# Main.net
KiCad netlist of a schematic drawn in Altium Designer
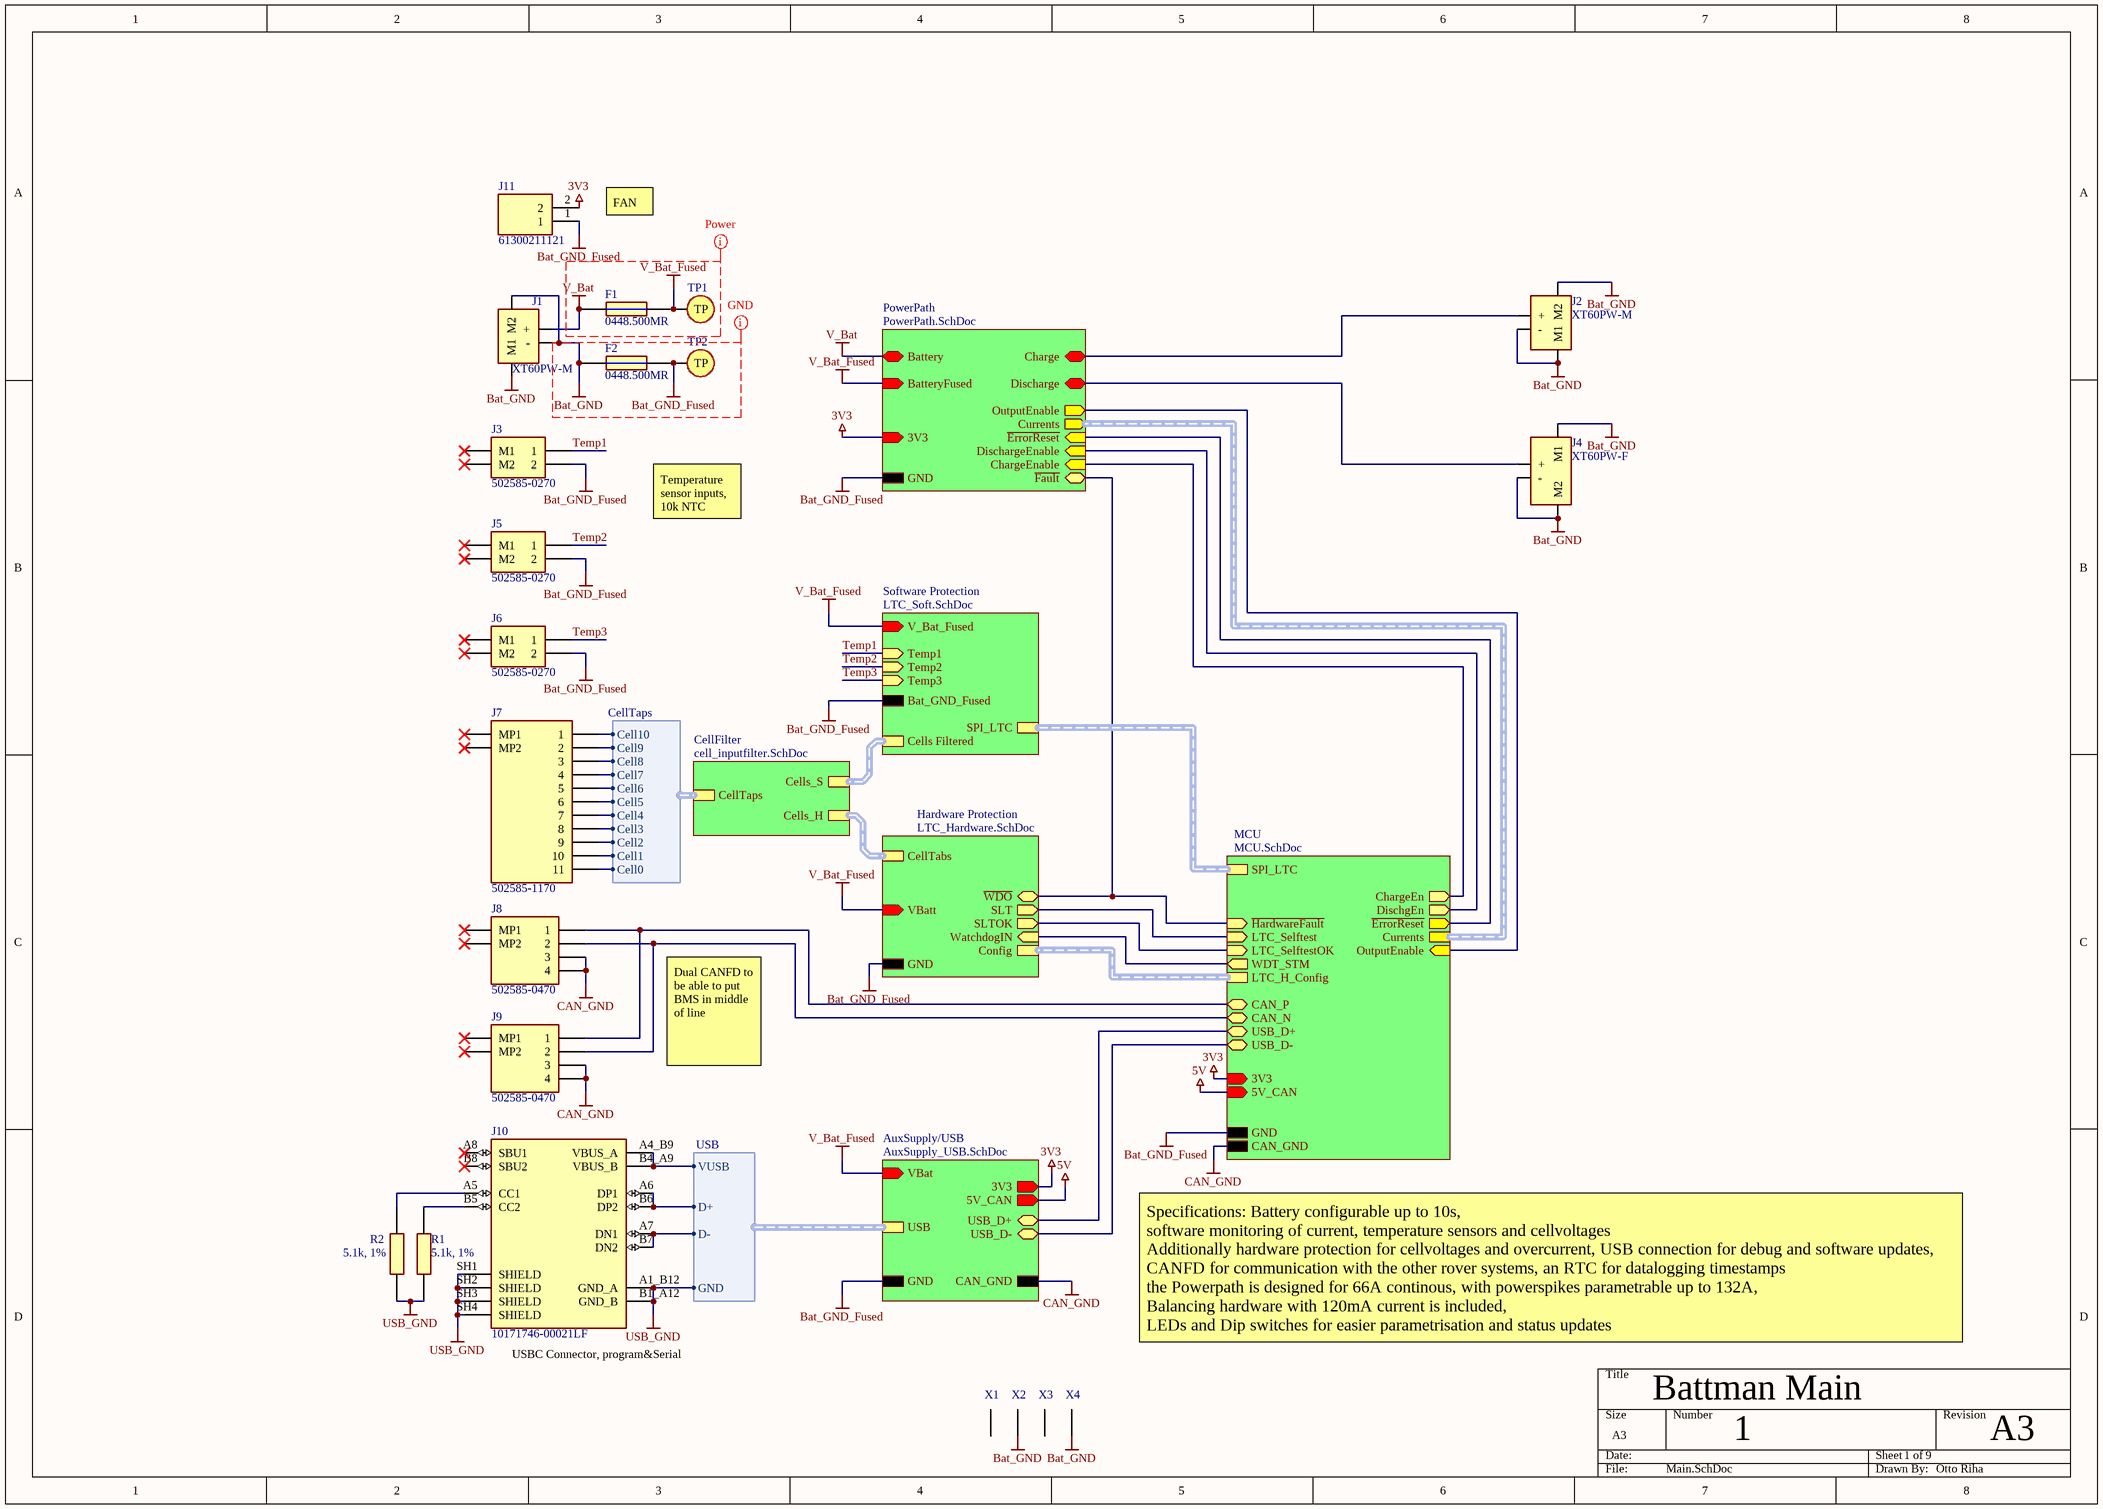
[diagram p0: Main.SchDoc]

(export (version "E")
  (design (tool "Eeschema 10.0.6"))
  (components
    (comp (ref "F1")
      (value "0448.500MR")
      (footprint "SamacSys:FUSC6127X294N")
      (description "Fuse")
      (fields (field (name "MOUSER PART NUMBER") "576-0448.500MR"))
      (libsource (lib "SamacSys") (part "0448.500MR"))
    )
    (comp (ref "F2")
      (value "0448.500MR")
      (footprint "SamacSys:FUSC6127X294N")
      (description "Fuse")
      (fields (field (name "MOUSER PART NUMBER") "576-0448.500MR"))
      (libsource (lib "SamacSys") (part "0448.500MR"))
    )
    (comp (ref "J1")
      (value "XT60PW-M")
      (footprint "SamacSys:XT60PWM")
      (description "Connector")
      (libsource (lib "SamacSys") (part "XT60PW-M"))
    )
    (comp (ref "J2")
      (value "XT60PW-M")
      (footprint "SamacSys:XT60PWM")
      (description "Connector")
      (libsource (lib "") (part "XT60PW-M_1"))
    )
    (comp (ref "J3")
      (value "502585-0270")
      (footprint "SamacSys:5025850270")
      (description "Connector")
      (fields (field (name "MOUSER PART NUMBER") "538-502585-0270"))
      (libsource (lib "SamacSys") (part "502585-0270"))
    )
    (comp (ref "J4")
      (value "XT60PW-F")
      (footprint "SamacSys:XT60PWF")
      (description "Connector")
      (libsource (lib "SamacSys") (part "XT60PW-F"))
    )
    (comp (ref "J5")
      (value "502585-0270")
      (footprint "SamacSys:5025850270")
      (description "Connector")
      (fields (field (name "MOUSER PART NUMBER") "538-502585-0270"))
      (libsource (lib "SamacSys") (part "502585-0270"))
    )
    (comp (ref "J6")
      (value "502585-0270")
      (footprint "SamacSys:5025850270")
      (description "Connector")
      (fields (field (name "MOUSER PART NUMBER") "538-502585-0270"))
      (libsource (lib "SamacSys") (part "502585-0270"))
    )
    (comp (ref "J7")
      (value "502585-1170")
      (footprint "SamacSys:5025851170")
      (description "Connector")
      (fields
        (field (name "MOUSER PART NUMBER") "538-502585-1170")
        (field (name "ARROW PART NUMBER") "502585-1070")
      )
      (libsource (lib "SamacSys") (part "502585-1170"))
    )
    (comp (ref "J8")
      (value "502585-0470")
      (footprint "SamacSys:5025850470")
      (description "Connector")
      (fields (field (name "MOUSER PART NUMBER") "538-502585-0470"))
      (libsource (lib "SamacSys") (part "502585-0470"))
    )
    (comp (ref "J9")
      (value "502585-0470")
      (footprint "SamacSys:5025850470")
      (description "Connector")
      (fields (field (name "MOUSER PART NUMBER") "538-502585-0470"))
      (libsource (lib "SamacSys") (part "502585-0470"))
    )
    (comp (ref "J10")
      (value "10171746-00021LF")
      (footprint "AMPHENOL_10171746-00021LF")
      (fields (field (name "MF") "Amphenol"))
      (libsource (lib "10171746-00021LF") (part "10171746-00021LF"))
    )
    (comp (ref "J11")
      (value "61300211121")
      (footprint "SamacSys:HDRV2W110P0X254_1X2_508X254X854P")
      (description "Connector")
      (fields (field (name "MOUSER PART NUMBER") "710-61300211121"))
      (libsource (lib "*") (part "61300211121"))
    )
    (comp (ref "R1")
      (value "5.1k, 1%")
      (footprint "SamacSys:RESC1608X55N")
      (description "Resistor 5.1k, 1%")
      (fields
        (field (name "MANUFACTURER_PART_NUMBER") "CRCW06035K10FKEBC")
        (field (name "MOUSER PART NUMBER") "71-CRCW06035K10FKEBC")
      )
      (libsource (lib "SamacSys") (part "CRCW06035K10FKEBC"))
    )
    (comp (ref "R2")
      (value "5.1k, 1%")
      (footprint "SamacSys:RESC1608X55N")
      (description "Resistor 5.1k, 1%")
      (fields
        (field (name "MANUFACTURER_PART_NUMBER") "CRCW06035K10FKEBC")
        (field (name "MOUSER PART NUMBER") "71-CRCW06035K10FKEBC")
      )
      (libsource (lib "SamacSys") (part "CRCW06035K10FKEBC"))
    )
    (comp (ref "TP1")
      (value "Testpoint")
      (footprint "Testpoint")
      (libsource (lib "SamacSys") (part "Testpoint"))
    )
    (comp (ref "TP2")
      (value "Testpoint")
      (footprint "Testpoint")
      (libsource (lib "SamacSys") (part "Testpoint"))
    )
    (comp (ref "X1")
      (value "Trou pour Vis M3 celon DIN912")
      (footprint "VisM3")
      (libsource (lib "SamacSys") (part "VisM3"))
    )
    (comp (ref "X2")
      (value "Trou pour Vis M3 celon DIN912")
      (footprint "VisM3")
      (libsource (lib "SamacSys") (part "VisM3"))
    )
    (comp (ref "X3")
      (value "Trou pour Vis M3 celon DIN912")
      (footprint "VisM3")
      (libsource (lib "SamacSys") (part "VisM3"))
    )
    (comp (ref "X4")
      (value "Trou pour Vis M3 celon DIN912")
      (footprint "VisM3")
      (libsource (lib "SamacSys") (part "VisM3"))
    )
  )
  (nets
    (net (code "3") (name "/CAN_N") (class "Default")
      (node (ref "J8") (pin "2") (pinfunction "2_2") (pintype "passive"))
      (node (ref "J9") (pin "2") (pinfunction "2_2") (pintype "passive"))
    )
    (net (code "4") (name "/CAN_P") (class "Default")
      (node (ref "J8") (pin "1") (pinfunction "1_1") (pintype "passive"))
      (node (ref "J9") (pin "1") (pinfunction "1_1") (pintype "passive"))
    )
    (net (code "5") (name "/Cell0") (class "Default")
      (node (ref "J7") (pin "11") (pinfunction "11_11") (pintype "passive"))
    )
    (net (code "6") (name "/Cell1") (class "Default")
      (node (ref "J7") (pin "10") (pinfunction "10_10") (pintype "passive"))
    )
    (net (code "7") (name "/Cell2") (class "Default")
      (node (ref "J7") (pin "9") (pinfunction "9_9") (pintype "passive"))
    )
    (net (code "8") (name "/Cell3") (class "Default")
      (node (ref "J7") (pin "8") (pinfunction "8_8") (pintype "passive"))
    )
    (net (code "9") (name "/Cell4") (class "Default")
      (node (ref "J7") (pin "7") (pinfunction "7_7") (pintype "passive"))
    )
    (net (code "10") (name "/Cell5") (class "Default")
      (node (ref "J7") (pin "6") (pinfunction "6_6") (pintype "passive"))
    )
    (net (code "11") (name "/Cell6") (class "Default")
      (node (ref "J7") (pin "5") (pinfunction "5_5") (pintype "passive"))
    )
    (net (code "12") (name "/Cell7") (class "Default")
      (node (ref "J7") (pin "4") (pinfunction "4_4") (pintype "passive"))
    )
    (net (code "13") (name "/Cell8") (class "Default")
      (node (ref "J7") (pin "3") (pinfunction "3_3") (pintype "passive"))
    )
    (net (code "14") (name "/Cell9") (class "Default")
      (node (ref "J7") (pin "2") (pinfunction "2_2") (pintype "passive"))
    )
    (net (code "15") (name "/Cell10") (class "Default")
      (node (ref "J7") (pin "1") (pinfunction "1_1") (pintype "passive"))
    )
    (net (code "18") (name "/Charge") (class "Default")
      (node (ref "J2") (pin "2") (pinfunction "+_2") (pintype "passive"))
    )
    (net (code "22") (name "/D+") (class "Default")
      (node (ref "J10") (pin "A6") (pinfunction "DP1_A6") (pintype "bidirectional"))
      (node (ref "J10") (pin "B6") (pinfunction "DP2_B6") (pintype "bidirectional"))
    )
    (net (code "23") (name "/D-") (class "Default")
      (node (ref "J10") (pin "A7") (pinfunction "DN1_A7") (pintype "bidirectional"))
      (node (ref "J10") (pin "B7") (pinfunction "DN2_B7") (pintype "bidirectional"))
    )
    (net (code "24") (name "/Discharge") (class "Default")
      (node (ref "J4") (pin "1") (pinfunction "+_1") (pintype "passive"))
    )
    (net (code "30") (name "/Temp1") (class "Default")
      (node (ref "J3") (pin "1") (pinfunction "1_1") (pintype "passive"))
    )
    (net (code "31") (name "/Temp2") (class "Default")
      (node (ref "J5") (pin "1") (pinfunction "1_1") (pintype "passive"))
    )
    (net (code "32") (name "/Temp3") (class "Default")
      (node (ref "J6") (pin "1") (pinfunction "1_1") (pintype "passive"))
    )
    (net (code "35") (name "/VUSB") (class "Default")
      (node (ref "J10") (pin "A4_B9") (pinfunction "VBUS_A_A4_B9") (pintype "power_in"))
      (node (ref "J10") (pin "B4_A9") (pinfunction "VBUS_B_B4_A9") (pintype "power_in"))
    )
    (net (code "41") (name "3V3") (class "Default")
      (node (ref "J11") (pin "2") (pinfunction "2_2") (pintype "passive"))
    )
    (net (code "43") (name "Bat_GND") (class "Default")
      (node (ref "F2") (pin "1") (pinfunction "1_1") (pintype "passive"))
      (node (ref "J1") (pin "1") (pinfunction "-_1") (pintype "passive"))
      (node (ref "J1") (pin "M1") (pinfunction "M1_M1") (pintype "passive"))
      (node (ref "J1") (pin "M2") (pinfunction "M2_M2") (pintype "passive"))
      (node (ref "J2") (pin "1") (pinfunction "-_1") (pintype "passive"))
      (node (ref "J2") (pin "M1") (pinfunction "M1_M1") (pintype "passive"))
      (node (ref "J2") (pin "M2") (pinfunction "M2_M2") (pintype "passive"))
      (node (ref "J4") (pin "2") (pinfunction "-_2") (pintype "passive"))
      (node (ref "J4") (pin "3") (pinfunction "M1_3") (pintype "passive"))
      (node (ref "J4") (pin "4") (pinfunction "M2_4") (pintype "passive"))
      (node (ref "X2") (pin "1") (pinfunction "M1_1") (pintype "passive"))
      (node (ref "X4") (pin "1") (pinfunction "M1_1") (pintype "passive"))
    )
    (net (code "44") (name "Bat_GND_Fused") (class "Default")
      (node (ref "F2") (pin "2") (pinfunction "2_2") (pintype "passive"))
      (node (ref "J11") (pin "1") (pinfunction "1_1") (pintype "passive"))
      (node (ref "J3") (pin "2") (pinfunction "2_2") (pintype "passive"))
      (node (ref "J5") (pin "2") (pinfunction "2_2") (pintype "passive"))
      (node (ref "J6") (pin "2") (pinfunction "2_2") (pintype "passive"))
      (node (ref "TP2") (pin "1") (pinfunction "TP_1") (pintype "passive"))
    )
    (net (code "45") (name "CAN_GND") (class "Default")
      (node (ref "J8") (pin "3") (pinfunction "3_3") (pintype "passive"))
      (node (ref "J8") (pin "4") (pinfunction "4_4") (pintype "passive"))
      (node (ref "J9") (pin "3") (pinfunction "3_3") (pintype "passive"))
      (node (ref "J9") (pin "4") (pinfunction "4_4") (pintype "passive"))
    )
    (net (code "46") (name "Net-(J10-CC1)") (class "Default")
      (node (ref "J10") (pin "A5") (pinfunction "CC1_A5") (pintype "bidirectional"))
      (node (ref "R2") (pin "2") (pinfunction "2_2") (pintype "passive"))
    )
    (net (code "47") (name "Net-(J10-CC2)") (class "Default")
      (node (ref "J10") (pin "B5") (pinfunction "CC2_B5") (pintype "bidirectional"))
      (node (ref "R1") (pin "2") (pinfunction "2_2") (pintype "passive"))
    )
    (net (code "48") (name "USB_GND") (class "Default")
      (node (ref "J10") (pin "A1_B12") (pinfunction "GND_A_A1_B12") (pintype "power_in"))
      (node (ref "J10") (pin "B1_A12") (pinfunction "GND_B_B1_A12") (pintype "power_in"))
      (node (ref "J10") (pin "SH1") (pinfunction "SHIELD_SH1") (pintype "passive"))
      (node (ref "J10") (pin "SH2") (pinfunction "SHIELD_SH2") (pintype "passive"))
      (node (ref "J10") (pin "SH3") (pinfunction "SHIELD_SH3") (pintype "passive"))
      (node (ref "J10") (pin "SH4") (pinfunction "SHIELD_SH4") (pintype "passive"))
      (node (ref "R1") (pin "1") (pinfunction "1_1") (pintype "passive"))
      (node (ref "R2") (pin "1") (pinfunction "1_1") (pintype "passive"))
    )
    (net (code "49") (name "V_Bat") (class "Default")
      (node (ref "F1") (pin "1") (pinfunction "1_1") (pintype "passive"))
      (node (ref "J1") (pin "2") (pinfunction "+_2") (pintype "passive"))
    )
    (net (code "50") (name "V_Bat_Fused") (class "Default")
      (node (ref "F1") (pin "2") (pinfunction "2_2") (pintype "passive"))
      (node (ref "TP1") (pin "1") (pinfunction "TP_1") (pintype "passive"))
    )
    (net (code "51") (name "unconnected-(J3-PadM1)") (class "Default")
      (node (ref "J3") (pin "M1") (pinfunction "M1_M1") (pintype "passive+no_connect"))
    )
    (net (code "52") (name "unconnected-(J3-PadM2)") (class "Default")
      (node (ref "J3") (pin "M2") (pinfunction "M2_M2") (pintype "passive+no_connect"))
    )
    (net (code "53") (name "unconnected-(J5-PadM1)") (class "Default")
      (node (ref "J5") (pin "M1") (pinfunction "M1_M1") (pintype "passive+no_connect"))
    )
    (net (code "54") (name "unconnected-(J5-PadM2)") (class "Default")
      (node (ref "J5") (pin "M2") (pinfunction "M2_M2") (pintype "passive+no_connect"))
    )
    (net (code "55") (name "unconnected-(J6-PadM1)") (class "Default")
      (node (ref "J6") (pin "M1") (pinfunction "M1_M1") (pintype "passive+no_connect"))
    )
    (net (code "56") (name "unconnected-(J6-PadM2)") (class "Default")
      (node (ref "J6") (pin "M2") (pinfunction "M2_M2") (pintype "passive+no_connect"))
    )
    (net (code "57") (name "unconnected-(J7-PadMP1)") (class "Default")
      (node (ref "J7") (pin "MP1") (pinfunction "MP1_MP1") (pintype "passive+no_connect"))
    )
    (net (code "58") (name "unconnected-(J7-PadMP2)") (class "Default")
      (node (ref "J7") (pin "MP2") (pinfunction "MP2_MP2") (pintype "passive+no_connect"))
    )
    (net (code "59") (name "unconnected-(J8-PadMP1)") (class "Default")
      (node (ref "J8") (pin "MP1") (pinfunction "MP1_MP1") (pintype "passive+no_connect"))
    )
    (net (code "60") (name "unconnected-(J8-PadMP2)") (class "Default")
      (node (ref "J8") (pin "MP2") (pinfunction "MP2_MP2") (pintype "passive+no_connect"))
    )
    (net (code "61") (name "unconnected-(J9-PadMP1)") (class "Default")
      (node (ref "J9") (pin "MP1") (pinfunction "MP1_MP1") (pintype "passive+no_connect"))
    )
    (net (code "62") (name "unconnected-(J9-PadMP2)") (class "Default")
      (node (ref "J9") (pin "MP2") (pinfunction "MP2_MP2") (pintype "passive+no_connect"))
    )
    (net (code "63") (name "unconnected-(J10-SBU1-PadA8)") (class "Default")
      (node (ref "J10") (pin "A8") (pinfunction "SBU1_A8") (pintype "bidirectional+no_connect"))
    )
    (net (code "64") (name "unconnected-(J10-SBU2-PadB8)") (class "Default")
      (node (ref "J10") (pin "B8") (pinfunction "SBU2_B8") (pintype "bidirectional+no_connect"))
    )
    (net (code "65") (name "unconnected-(X1-M1-Pad1)") (class "Default")
      (node (ref "X1") (pin "1") (pinfunction "M1_1") (pintype "passive"))
    )
    (net (code "66") (name "unconnected-(X3-M1-Pad1)") (class "Default")
      (node (ref "X3") (pin "1") (pinfunction "M1_1") (pintype "passive"))
    )
  )
)
